# LED.net
KiCad netlist of a schematic drawn in Altium Designer
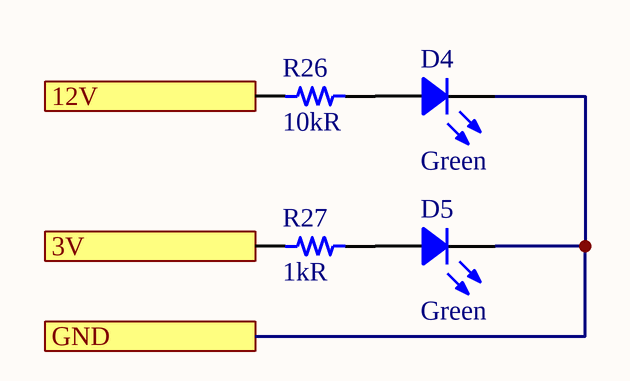
[diagram p0: LED.SchDoc]

(export (version "E")
  (design (tool "Eeschema 10.0.6"))
  (components
    (comp (ref "D4")
      (value "Green")
      (footprint "LED 0603_1608 GREEN")
      (description "GREEN, D=564NM, IV=75MCD")
      (fields (field (name "PART NUMBER") "SECU1413C-TG20") (field (name "MANUFACTURER") "Sanken"))
      (libsource (lib "Celestial Altium Library - altium_library") (part "LED"))
    )
    (comp (ref "D5")
      (value "Green")
      (footprint "LED 0603_1608 GREEN")
      (description "GREEN, D=564NM, IV=75MCD")
      (fields (field (name "PART NUMBER") "SECU1413C-TG20") (field (name "MANUFACTURER") "Sanken"))
      (libsource (lib "Celestial Altium Library - altium_library") (part "LED"))
    )
    (comp (ref "R26")
      (value "10kR")
      (footprint "RES 0402_1005")
      (description "RES 249K OHM 0.1% 1/10W 0402")
      (fields
        (field (name "PART NUMBER") "RP73PF1E249KBTD")
        (field (name "MANUFACTURER") "TE Connectivity Passive Product")
      )
      (libsource (lib "Celestial Altium Library - altium_library") (part "Resistor"))
    )
    (comp (ref "R27")
      (value "1kR")
      (footprint "RES 0402_1005")
      (description "RES 249K OHM 0.1% 1/10W 0402")
      (fields
        (field (name "PART NUMBER") "RP73PF1E249KBTD")
        (field (name "MANUFACTURER") "TE Connectivity Passive Product")
      )
      (libsource (lib "Celestial Altium Library - altium_library") (part "Resistor"))
    )
  )
  (nets
    (net (code "1") (name "/3V") (class "Default")
      (node (ref "R27") (pin "2") (pinfunction "2_2") (pintype "passive"))
    )
    (net (code "2") (name "/12V") (class "Default")
      (node (ref "R26") (pin "2") (pinfunction "2_2") (pintype "passive"))
    )
    (net (code "3") (name "/GND") (class "Default")
      (node (ref "D4") (pin "2") (pinfunction "2_2") (pintype "passive"))
      (node (ref "D5") (pin "2") (pinfunction "2_2") (pintype "passive"))
    )
    (net (code "4") (name "Net-(D4-Pad1)") (class "Default")
      (node (ref "D4") (pin "1") (pinfunction "1_1") (pintype "passive"))
      (node (ref "R26") (pin "1") (pinfunction "1_1") (pintype "passive"))
    )
    (net (code "5") (name "Net-(D5-Pad1)") (class "Default")
      (node (ref "D5") (pin "1") (pinfunction "1_1") (pintype "passive"))
      (node (ref "R27") (pin "1") (pinfunction "1_1") (pintype "passive"))
    )
  )
)
